# Reed_Switches.net
KiCad netlist of a schematic drawn in Altium Designer
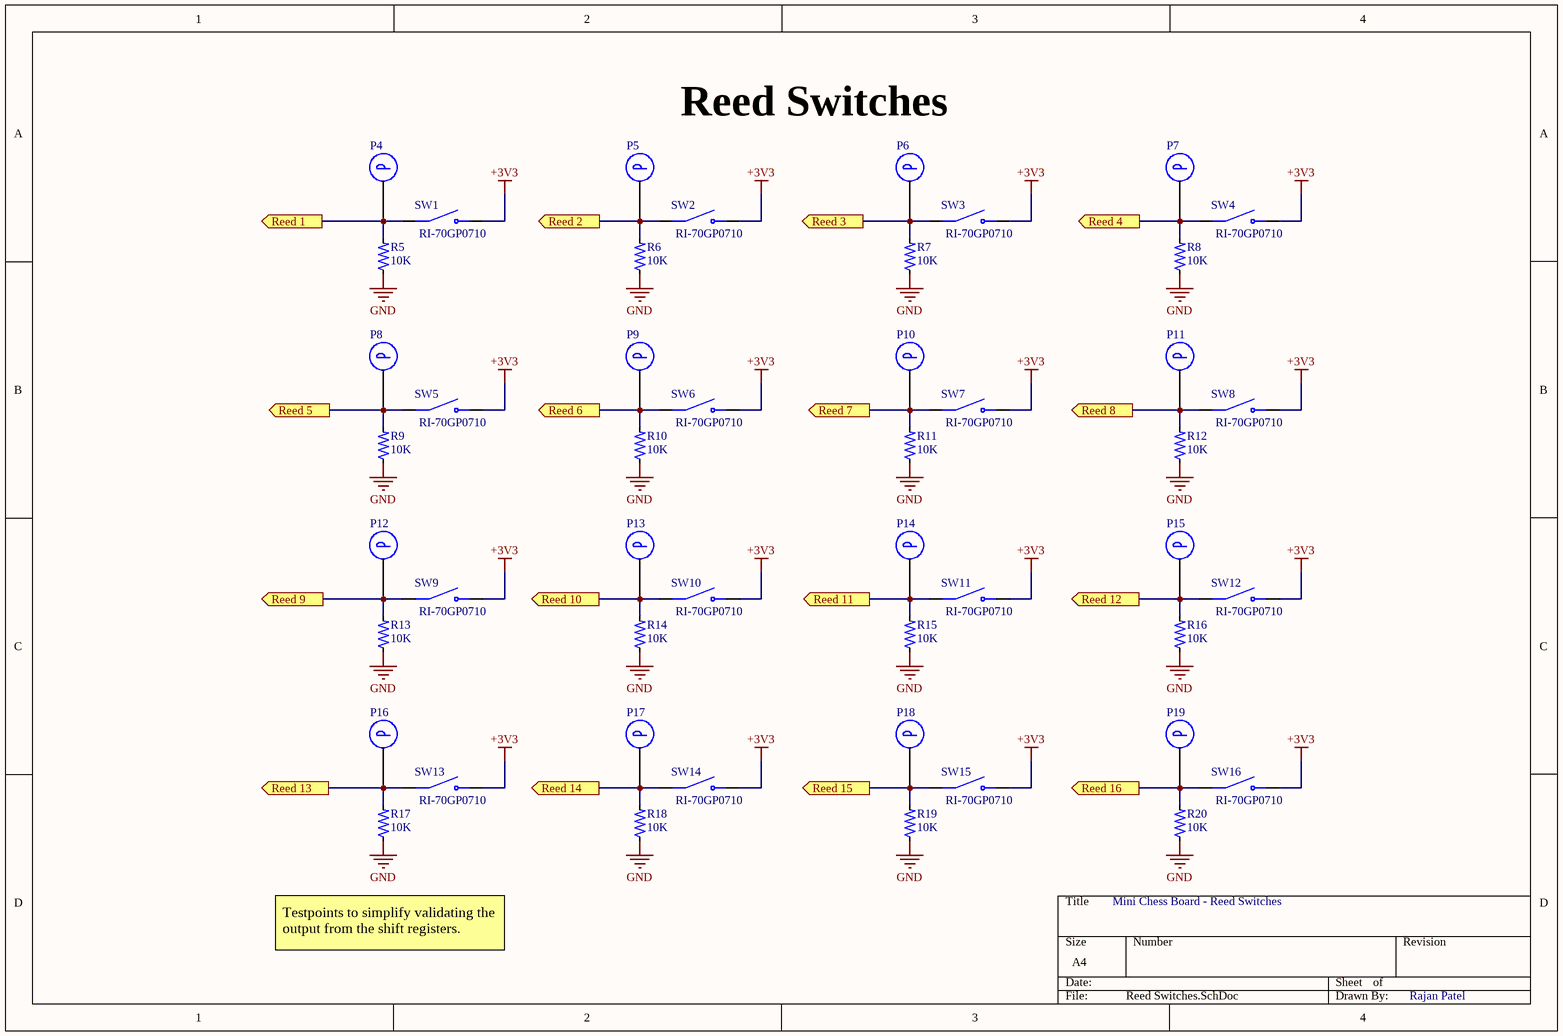
[diagram p0: Reed Switches.SchDoc]

(export (version "E")
  (design (tool "Eeschema 10.0.6"))
  (components
    (comp (ref "P4")
      (value "Probe_5019")
      (footprint "Testpoint")
      (description "Phosphor Bronze Contact Miniature Silver Plated Surface Mount Test Points")
      (fields
        (field (name "MANUFACTURER") "Keystone Electronics")
        (field (name "MANUFACTURER PART NUMBER") "5019")
      )
      (libsource (lib "MiniChessBoardSchLib") (part "Probe_5019"))
    )
    (comp (ref "P5")
      (value "Probe_5019")
      (footprint "Testpoint")
      (description "Phosphor Bronze Contact Miniature Silver Plated Surface Mount Test Points")
      (fields
        (field (name "MANUFACTURER") "Keystone Electronics")
        (field (name "MANUFACTURER PART NUMBER") "5019")
      )
      (libsource (lib "MiniChessBoardSchLib") (part "Probe_5019"))
    )
    (comp (ref "P6")
      (value "Probe_5019")
      (footprint "Testpoint")
      (description "Phosphor Bronze Contact Miniature Silver Plated Surface Mount Test Points")
      (fields
        (field (name "MANUFACTURER") "Keystone Electronics")
        (field (name "MANUFACTURER PART NUMBER") "5019")
      )
      (libsource (lib "MiniChessBoardSchLib") (part "Probe_5019"))
    )
    (comp (ref "P7")
      (value "Probe_5019")
      (footprint "Testpoint")
      (description "Phosphor Bronze Contact Miniature Silver Plated Surface Mount Test Points")
      (fields
        (field (name "MANUFACTURER") "Keystone Electronics")
        (field (name "MANUFACTURER PART NUMBER") "5019")
      )
      (libsource (lib "MiniChessBoardSchLib") (part "Probe_5019"))
    )
    (comp (ref "P8")
      (value "Probe_5019")
      (footprint "Testpoint")
      (description "Phosphor Bronze Contact Miniature Silver Plated Surface Mount Test Points")
      (fields
        (field (name "MANUFACTURER") "Keystone Electronics")
        (field (name "MANUFACTURER PART NUMBER") "5019")
      )
      (libsource (lib "MiniChessBoardSchLib") (part "Probe_5019"))
    )
    (comp (ref "P9")
      (value "Probe_5019")
      (footprint "Testpoint")
      (description "Phosphor Bronze Contact Miniature Silver Plated Surface Mount Test Points")
      (fields
        (field (name "MANUFACTURER") "Keystone Electronics")
        (field (name "MANUFACTURER PART NUMBER") "5019")
      )
      (libsource (lib "MiniChessBoardSchLib") (part "Probe_5019"))
    )
    (comp (ref "P10")
      (value "Probe_5019")
      (footprint "Testpoint")
      (description "Phosphor Bronze Contact Miniature Silver Plated Surface Mount Test Points")
      (fields
        (field (name "MANUFACTURER") "Keystone Electronics")
        (field (name "MANUFACTURER PART NUMBER") "5019")
      )
      (libsource (lib "MiniChessBoardSchLib") (part "Probe_5019"))
    )
    (comp (ref "P11")
      (value "Probe_5019")
      (footprint "Testpoint")
      (description "Phosphor Bronze Contact Miniature Silver Plated Surface Mount Test Points")
      (fields
        (field (name "MANUFACTURER") "Keystone Electronics")
        (field (name "MANUFACTURER PART NUMBER") "5019")
      )
      (libsource (lib "MiniChessBoardSchLib") (part "Probe_5019"))
    )
    (comp (ref "P12")
      (value "Probe_5019")
      (footprint "Testpoint")
      (description "Phosphor Bronze Contact Miniature Silver Plated Surface Mount Test Points")
      (fields
        (field (name "MANUFACTURER") "Keystone Electronics")
        (field (name "MANUFACTURER PART NUMBER") "5019")
      )
      (libsource (lib "MiniChessBoardSchLib") (part "Probe_5019"))
    )
    (comp (ref "P13")
      (value "Probe_5019")
      (footprint "Testpoint")
      (description "Phosphor Bronze Contact Miniature Silver Plated Surface Mount Test Points")
      (fields
        (field (name "MANUFACTURER") "Keystone Electronics")
        (field (name "MANUFACTURER PART NUMBER") "5019")
      )
      (libsource (lib "MiniChessBoardSchLib") (part "Probe_5019"))
    )
    (comp (ref "P14")
      (value "Probe_5019")
      (footprint "Testpoint")
      (description "Phosphor Bronze Contact Miniature Silver Plated Surface Mount Test Points")
      (fields
        (field (name "MANUFACTURER") "Keystone Electronics")
        (field (name "MANUFACTURER PART NUMBER") "5019")
      )
      (libsource (lib "MiniChessBoardSchLib") (part "Probe_5019"))
    )
    (comp (ref "P15")
      (value "Probe_5019")
      (footprint "Testpoint")
      (description "Phosphor Bronze Contact Miniature Silver Plated Surface Mount Test Points")
      (fields
        (field (name "MANUFACTURER") "Keystone Electronics")
        (field (name "MANUFACTURER PART NUMBER") "5019")
      )
      (libsource (lib "MiniChessBoardSchLib") (part "Probe_5019"))
    )
    (comp (ref "P16")
      (value "Probe_5019")
      (footprint "Testpoint")
      (description "Phosphor Bronze Contact Miniature Silver Plated Surface Mount Test Points")
      (fields
        (field (name "MANUFACTURER") "Keystone Electronics")
        (field (name "MANUFACTURER PART NUMBER") "5019")
      )
      (libsource (lib "MiniChessBoardSchLib") (part "Probe_5019"))
    )
    (comp (ref "P17")
      (value "Probe_5019")
      (footprint "Testpoint")
      (description "Phosphor Bronze Contact Miniature Silver Plated Surface Mount Test Points")
      (fields
        (field (name "MANUFACTURER") "Keystone Electronics")
        (field (name "MANUFACTURER PART NUMBER") "5019")
      )
      (libsource (lib "MiniChessBoardSchLib") (part "Probe_5019"))
    )
    (comp (ref "P18")
      (value "Probe_5019")
      (footprint "Testpoint")
      (description "Phosphor Bronze Contact Miniature Silver Plated Surface Mount Test Points")
      (fields
        (field (name "MANUFACTURER") "Keystone Electronics")
        (field (name "MANUFACTURER PART NUMBER") "5019")
      )
      (libsource (lib "MiniChessBoardSchLib") (part "Probe_5019"))
    )
    (comp (ref "P19")
      (value "Probe_5019")
      (footprint "Testpoint")
      (description "Phosphor Bronze Contact Miniature Silver Plated Surface Mount Test Points")
      (fields
        (field (name "MANUFACTURER") "Keystone Electronics")
        (field (name "MANUFACTURER PART NUMBER") "5019")
      )
      (libsource (lib "MiniChessBoardSchLib") (part "Probe_5019"))
    )
    (comp (ref "R5")
      (value "10K")
      (footprint "res 0805")
      (fields
        (field (name "MP") "2-2176053-2")
        (field (name "MF") "TE Connectivity")
        (field (name "TOLERANCE") "1%")
      )
      (libsource (lib "ChessBoardSchLib") (part "Resistor 0805"))
    )
    (comp (ref "R6")
      (value "10K")
      (footprint "res 0805")
      (fields
        (field (name "MP") "2-2176053-2")
        (field (name "MF") "TE Connectivity")
        (field (name "TOLERANCE") "1%")
      )
      (libsource (lib "ChessBoardSchLib") (part "Resistor 0805"))
    )
    (comp (ref "R7")
      (value "10K")
      (footprint "res 0805")
      (fields
        (field (name "MP") "2-2176053-2")
        (field (name "MF") "TE Connectivity")
        (field (name "TOLERANCE") "1%")
      )
      (libsource (lib "ChessBoardSchLib") (part "Resistor 0805"))
    )
    (comp (ref "R8")
      (value "10K")
      (footprint "res 0805")
      (fields
        (field (name "MP") "2-2176053-2")
        (field (name "MF") "TE Connectivity")
        (field (name "TOLERANCE") "1%")
      )
      (libsource (lib "ChessBoardSchLib") (part "Resistor 0805"))
    )
    (comp (ref "R9")
      (value "10K")
      (footprint "res 0805")
      (fields
        (field (name "MP") "2-2176053-2")
        (field (name "MF") "TE Connectivity")
        (field (name "TOLERANCE") "1%")
      )
      (libsource (lib "ChessBoardSchLib") (part "Resistor 0805"))
    )
    (comp (ref "R10")
      (value "10K")
      (footprint "res 0805")
      (fields
        (field (name "MP") "2-2176053-2")
        (field (name "MF") "TE Connectivity")
        (field (name "TOLERANCE") "1%")
      )
      (libsource (lib "ChessBoardSchLib") (part "Resistor 0805"))
    )
    (comp (ref "R11")
      (value "10K")
      (footprint "res 0805")
      (fields
        (field (name "MP") "2-2176053-2")
        (field (name "MF") "TE Connectivity")
        (field (name "TOLERANCE") "1%")
      )
      (libsource (lib "ChessBoardSchLib") (part "Resistor 0805"))
    )
    (comp (ref "R12")
      (value "10K")
      (footprint "res 0805")
      (fields
        (field (name "MP") "2-2176053-2")
        (field (name "MF") "TE Connectivity")
        (field (name "TOLERANCE") "1%")
      )
      (libsource (lib "ChessBoardSchLib") (part "Resistor 0805"))
    )
    (comp (ref "R13")
      (value "10K")
      (footprint "res 0805")
      (fields
        (field (name "MP") "2-2176053-2")
        (field (name "MF") "TE Connectivity")
        (field (name "TOLERANCE") "1%")
      )
      (libsource (lib "ChessBoardSchLib") (part "Resistor 0805"))
    )
    (comp (ref "R14")
      (value "10K")
      (footprint "res 0805")
      (fields
        (field (name "MP") "2-2176053-2")
        (field (name "MF") "TE Connectivity")
        (field (name "TOLERANCE") "1%")
      )
      (libsource (lib "ChessBoardSchLib") (part "Resistor 0805"))
    )
    (comp (ref "R15")
      (value "10K")
      (footprint "res 0805")
      (fields
        (field (name "MP") "2-2176053-2")
        (field (name "MF") "TE Connectivity")
        (field (name "TOLERANCE") "1%")
      )
      (libsource (lib "ChessBoardSchLib") (part "Resistor 0805"))
    )
    (comp (ref "R16")
      (value "10K")
      (footprint "res 0805")
      (fields
        (field (name "MP") "2-2176053-2")
        (field (name "MF") "TE Connectivity")
        (field (name "TOLERANCE") "1%")
      )
      (libsource (lib "ChessBoardSchLib") (part "Resistor 0805"))
    )
    (comp (ref "R17")
      (value "10K")
      (footprint "res 0805")
      (fields
        (field (name "MP") "2-2176053-2")
        (field (name "MF") "TE Connectivity")
        (field (name "TOLERANCE") "1%")
      )
      (libsource (lib "ChessBoardSchLib") (part "Resistor 0805"))
    )
    (comp (ref "R18")
      (value "10K")
      (footprint "res 0805")
      (fields
        (field (name "MP") "2-2176053-2")
        (field (name "MF") "TE Connectivity")
        (field (name "TOLERANCE") "1%")
      )
      (libsource (lib "ChessBoardSchLib") (part "Resistor 0805"))
    )
    (comp (ref "R19")
      (value "10K")
      (footprint "res 0805")
      (fields
        (field (name "MP") "2-2176053-2")
        (field (name "MF") "TE Connectivity")
        (field (name "TOLERANCE") "1%")
      )
      (libsource (lib "ChessBoardSchLib") (part "Resistor 0805"))
    )
    (comp (ref "R20")
      (value "10K")
      (footprint "res 0805")
      (fields
        (field (name "MP") "2-2176053-2")
        (field (name "MF") "TE Connectivity")
        (field (name "TOLERANCE") "1%")
      )
      (libsource (lib "ChessBoardSchLib") (part "Resistor 0805"))
    )
    (comp (ref "SW1")
      (value "RI-70GP0710")
      (footprint "RI-70GP0710")
      (description "Switch Reed Spst-no 500MA 120V")
      (fields (field (name "MANUFACTURER") "Comus"))
      (libsource (lib "ChessBoardSchLib") (part "RI-70GP0710"))
    )
    (comp (ref "SW2")
      (value "RI-70GP0710")
      (footprint "RI-70GP0710")
      (description "Switch Reed Spst-no 500MA 120V")
      (fields (field (name "MANUFACTURER") "Comus"))
      (libsource (lib "ChessBoardSchLib") (part "RI-70GP0710"))
    )
    (comp (ref "SW3")
      (value "RI-70GP0710")
      (footprint "RI-70GP0710")
      (description "Switch Reed Spst-no 500MA 120V")
      (fields (field (name "MANUFACTURER") "Comus"))
      (libsource (lib "ChessBoardSchLib") (part "RI-70GP0710"))
    )
    (comp (ref "SW4")
      (value "RI-70GP0710")
      (footprint "RI-70GP0710")
      (description "Switch Reed Spst-no 500MA 120V")
      (fields (field (name "MANUFACTURER") "Comus"))
      (libsource (lib "ChessBoardSchLib") (part "RI-70GP0710"))
    )
    (comp (ref "SW5")
      (value "RI-70GP0710")
      (footprint "RI-70GP0710")
      (description "Switch Reed Spst-no 500MA 120V")
      (fields (field (name "MANUFACTURER") "Comus"))
      (libsource (lib "ChessBoardSchLib") (part "RI-70GP0710"))
    )
    (comp (ref "SW6")
      (value "RI-70GP0710")
      (footprint "RI-70GP0710")
      (description "Switch Reed Spst-no 500MA 120V")
      (fields (field (name "MANUFACTURER") "Comus"))
      (libsource (lib "ChessBoardSchLib") (part "RI-70GP0710"))
    )
    (comp (ref "SW7")
      (value "RI-70GP0710")
      (footprint "RI-70GP0710")
      (description "Switch Reed Spst-no 500MA 120V")
      (fields (field (name "MANUFACTURER") "Comus"))
      (libsource (lib "ChessBoardSchLib") (part "RI-70GP0710"))
    )
    (comp (ref "SW8")
      (value "RI-70GP0710")
      (footprint "RI-70GP0710")
      (description "Switch Reed Spst-no 500MA 120V")
      (fields (field (name "MANUFACTURER") "Comus"))
      (libsource (lib "ChessBoardSchLib") (part "RI-70GP0710"))
    )
    (comp (ref "SW9")
      (value "RI-70GP0710")
      (footprint "RI-70GP0710")
      (description "Switch Reed Spst-no 500MA 120V")
      (fields (field (name "MANUFACTURER") "Comus"))
      (libsource (lib "ChessBoardSchLib") (part "RI-70GP0710"))
    )
    (comp (ref "SW10")
      (value "RI-70GP0710")
      (footprint "RI-70GP0710")
      (description "Switch Reed Spst-no 500MA 120V")
      (fields (field (name "MANUFACTURER") "Comus"))
      (libsource (lib "ChessBoardSchLib") (part "RI-70GP0710"))
    )
    (comp (ref "SW11")
      (value "RI-70GP0710")
      (footprint "RI-70GP0710")
      (description "Switch Reed Spst-no 500MA 120V")
      (fields (field (name "MANUFACTURER") "Comus"))
      (libsource (lib "ChessBoardSchLib") (part "RI-70GP0710"))
    )
    (comp (ref "SW12")
      (value "RI-70GP0710")
      (footprint "RI-70GP0710")
      (description "Switch Reed Spst-no 500MA 120V")
      (fields (field (name "MANUFACTURER") "Comus"))
      (libsource (lib "ChessBoardSchLib") (part "RI-70GP0710"))
    )
    (comp (ref "SW13")
      (value "RI-70GP0710")
      (footprint "RI-70GP0710")
      (description "Switch Reed Spst-no 500MA 120V")
      (fields (field (name "MANUFACTURER") "Comus"))
      (libsource (lib "ChessBoardSchLib") (part "RI-70GP0710"))
    )
    (comp (ref "SW14")
      (value "RI-70GP0710")
      (footprint "RI-70GP0710")
      (description "Switch Reed Spst-no 500MA 120V")
      (fields (field (name "MANUFACTURER") "Comus"))
      (libsource (lib "ChessBoardSchLib") (part "RI-70GP0710"))
    )
    (comp (ref "SW15")
      (value "RI-70GP0710")
      (footprint "RI-70GP0710")
      (description "Switch Reed Spst-no 500MA 120V")
      (fields (field (name "MANUFACTURER") "Comus"))
      (libsource (lib "ChessBoardSchLib") (part "RI-70GP0710"))
    )
    (comp (ref "SW16")
      (value "RI-70GP0710")
      (footprint "RI-70GP0710")
      (description "Switch Reed Spst-no 500MA 120V")
      (fields (field (name "MANUFACTURER") "Comus"))
      (libsource (lib "ChessBoardSchLib") (part "RI-70GP0710"))
    )
  )
  (nets
    (net (code "1") (name "+3V3") (class "Default")
      (node (ref "SW1") (pin "2") (pinfunction "NO_2") (pintype "passive"))
      (node (ref "SW10") (pin "2") (pinfunction "NO_2") (pintype "passive"))
      (node (ref "SW11") (pin "2") (pinfunction "NO_2") (pintype "passive"))
      (node (ref "SW12") (pin "2") (pinfunction "NO_2") (pintype "passive"))
      (node (ref "SW13") (pin "2") (pinfunction "NO_2") (pintype "passive"))
      (node (ref "SW14") (pin "2") (pinfunction "NO_2") (pintype "passive"))
      (node (ref "SW15") (pin "2") (pinfunction "NO_2") (pintype "passive"))
      (node (ref "SW16") (pin "2") (pinfunction "NO_2") (pintype "passive"))
      (node (ref "SW2") (pin "2") (pinfunction "NO_2") (pintype "passive"))
      (node (ref "SW3") (pin "2") (pinfunction "NO_2") (pintype "passive"))
      (node (ref "SW4") (pin "2") (pinfunction "NO_2") (pintype "passive"))
      (node (ref "SW5") (pin "2") (pinfunction "NO_2") (pintype "passive"))
      (node (ref "SW6") (pin "2") (pinfunction "NO_2") (pintype "passive"))
      (node (ref "SW7") (pin "2") (pinfunction "NO_2") (pintype "passive"))
      (node (ref "SW8") (pin "2") (pinfunction "NO_2") (pintype "passive"))
      (node (ref "SW9") (pin "2") (pinfunction "NO_2") (pintype "passive"))
    )
    (net (code "2") (name "/Reed 1") (class "Default")
      (node (ref "P4") (pin "1") (pinfunction "1_1") (pintype "passive"))
      (node (ref "R5") (pin "2") (pinfunction "2_2") (pintype "passive"))
      (node (ref "SW1") (pin "1") (pinfunction "COM_1") (pintype "passive"))
    )
    (net (code "3") (name "/Reed 2") (class "Default")
      (node (ref "P5") (pin "1") (pinfunction "1_1") (pintype "passive"))
      (node (ref "R6") (pin "2") (pinfunction "2_2") (pintype "passive"))
      (node (ref "SW2") (pin "1") (pinfunction "COM_1") (pintype "passive"))
    )
    (net (code "4") (name "/Reed 3") (class "Default")
      (node (ref "P6") (pin "1") (pinfunction "1_1") (pintype "passive"))
      (node (ref "R7") (pin "2") (pinfunction "2_2") (pintype "passive"))
      (node (ref "SW3") (pin "1") (pinfunction "COM_1") (pintype "passive"))
    )
    (net (code "5") (name "/Reed 4") (class "Default")
      (node (ref "P7") (pin "1") (pinfunction "1_1") (pintype "passive"))
      (node (ref "R8") (pin "2") (pinfunction "2_2") (pintype "passive"))
      (node (ref "SW4") (pin "1") (pinfunction "COM_1") (pintype "passive"))
    )
    (net (code "6") (name "/Reed 5") (class "Default")
      (node (ref "P8") (pin "1") (pinfunction "1_1") (pintype "passive"))
      (node (ref "R9") (pin "2") (pinfunction "2_2") (pintype "passive"))
      (node (ref "SW5") (pin "1") (pinfunction "COM_1") (pintype "passive"))
    )
    (net (code "7") (name "/Reed 6") (class "Default")
      (node (ref "P9") (pin "1") (pinfunction "1_1") (pintype "passive"))
      (node (ref "R10") (pin "2") (pinfunction "2_2") (pintype "passive"))
      (node (ref "SW6") (pin "1") (pinfunction "COM_1") (pintype "passive"))
    )
    (net (code "8") (name "/Reed 7") (class "Default")
      (node (ref "P10") (pin "1") (pinfunction "1_1") (pintype "passive"))
      (node (ref "R11") (pin "2") (pinfunction "2_2") (pintype "passive"))
      (node (ref "SW7") (pin "1") (pinfunction "COM_1") (pintype "passive"))
    )
    (net (code "9") (name "/Reed 8") (class "Default")
      (node (ref "P11") (pin "1") (pinfunction "1_1") (pintype "passive"))
      (node (ref "R12") (pin "2") (pinfunction "2_2") (pintype "passive"))
      (node (ref "SW8") (pin "1") (pinfunction "COM_1") (pintype "passive"))
    )
    (net (code "10") (name "/Reed 9") (class "Default")
      (node (ref "P12") (pin "1") (pinfunction "1_1") (pintype "passive"))
      (node (ref "R13") (pin "2") (pinfunction "2_2") (pintype "passive"))
      (node (ref "SW9") (pin "1") (pinfunction "COM_1") (pintype "passive"))
    )
    (net (code "11") (name "/Reed 10") (class "Default")
      (node (ref "P13") (pin "1") (pinfunction "1_1") (pintype "passive"))
      (node (ref "R14") (pin "2") (pinfunction "2_2") (pintype "passive"))
      (node (ref "SW10") (pin "1") (pinfunction "COM_1") (pintype "passive"))
    )
    (net (code "12") (name "/Reed 11") (class "Default")
      (node (ref "P14") (pin "1") (pinfunction "1_1") (pintype "passive"))
      (node (ref "R15") (pin "2") (pinfunction "2_2") (pintype "passive"))
      (node (ref "SW11") (pin "1") (pinfunction "COM_1") (pintype "passive"))
    )
    (net (code "13") (name "/Reed 12") (class "Default")
      (node (ref "P15") (pin "1") (pinfunction "1_1") (pintype "passive"))
      (node (ref "R16") (pin "2") (pinfunction "2_2") (pintype "passive"))
      (node (ref "SW12") (pin "1") (pinfunction "COM_1") (pintype "passive"))
    )
    (net (code "14") (name "/Reed 13") (class "Default")
      (node (ref "P16") (pin "1") (pinfunction "1_1") (pintype "passive"))
      (node (ref "R17") (pin "2") (pinfunction "2_2") (pintype "passive"))
      (node (ref "SW13") (pin "1") (pinfunction "COM_1") (pintype "passive"))
    )
    (net (code "15") (name "/Reed 14") (class "Default")
      (node (ref "P17") (pin "1") (pinfunction "1_1") (pintype "passive"))
      (node (ref "R18") (pin "2") (pinfunction "2_2") (pintype "passive"))
      (node (ref "SW14") (pin "1") (pinfunction "COM_1") (pintype "passive"))
    )
    (net (code "16") (name "/Reed 15") (class "Default")
      (node (ref "P18") (pin "1") (pinfunction "1_1") (pintype "passive"))
      (node (ref "R19") (pin "2") (pinfunction "2_2") (pintype "passive"))
      (node (ref "SW15") (pin "1") (pinfunction "COM_1") (pintype "passive"))
    )
    (net (code "17") (name "/Reed 16") (class "Default")
      (node (ref "P19") (pin "1") (pinfunction "1_1") (pintype "passive"))
      (node (ref "R20") (pin "2") (pinfunction "2_2") (pintype "passive"))
      (node (ref "SW16") (pin "1") (pinfunction "COM_1") (pintype "passive"))
    )
    (net (code "18") (name "GND") (class "Default")
      (node (ref "R10") (pin "1") (pinfunction "1_1") (pintype "passive"))
      (node (ref "R11") (pin "1") (pinfunction "1_1") (pintype "passive"))
      (node (ref "R12") (pin "1") (pinfunction "1_1") (pintype "passive"))
      (node (ref "R13") (pin "1") (pinfunction "1_1") (pintype "passive"))
      (node (ref "R14") (pin "1") (pinfunction "1_1") (pintype "passive"))
      (node (ref "R15") (pin "1") (pinfunction "1_1") (pintype "passive"))
      (node (ref "R16") (pin "1") (pinfunction "1_1") (pintype "passive"))
      (node (ref "R17") (pin "1") (pinfunction "1_1") (pintype "passive"))
      (node (ref "R18") (pin "1") (pinfunction "1_1") (pintype "passive"))
      (node (ref "R19") (pin "1") (pinfunction "1_1") (pintype "passive"))
      (node (ref "R20") (pin "1") (pinfunction "1_1") (pintype "passive"))
      (node (ref "R5") (pin "1") (pinfunction "1_1") (pintype "passive"))
      (node (ref "R6") (pin "1") (pinfunction "1_1") (pintype "passive"))
      (node (ref "R7") (pin "1") (pinfunction "1_1") (pintype "passive"))
      (node (ref "R8") (pin "1") (pinfunction "1_1") (pintype "passive"))
      (node (ref "R9") (pin "1") (pinfunction "1_1") (pintype "passive"))
    )
  )
)
